# HRT1.net
KiCad netlist of a schematic drawn in Altium Designer
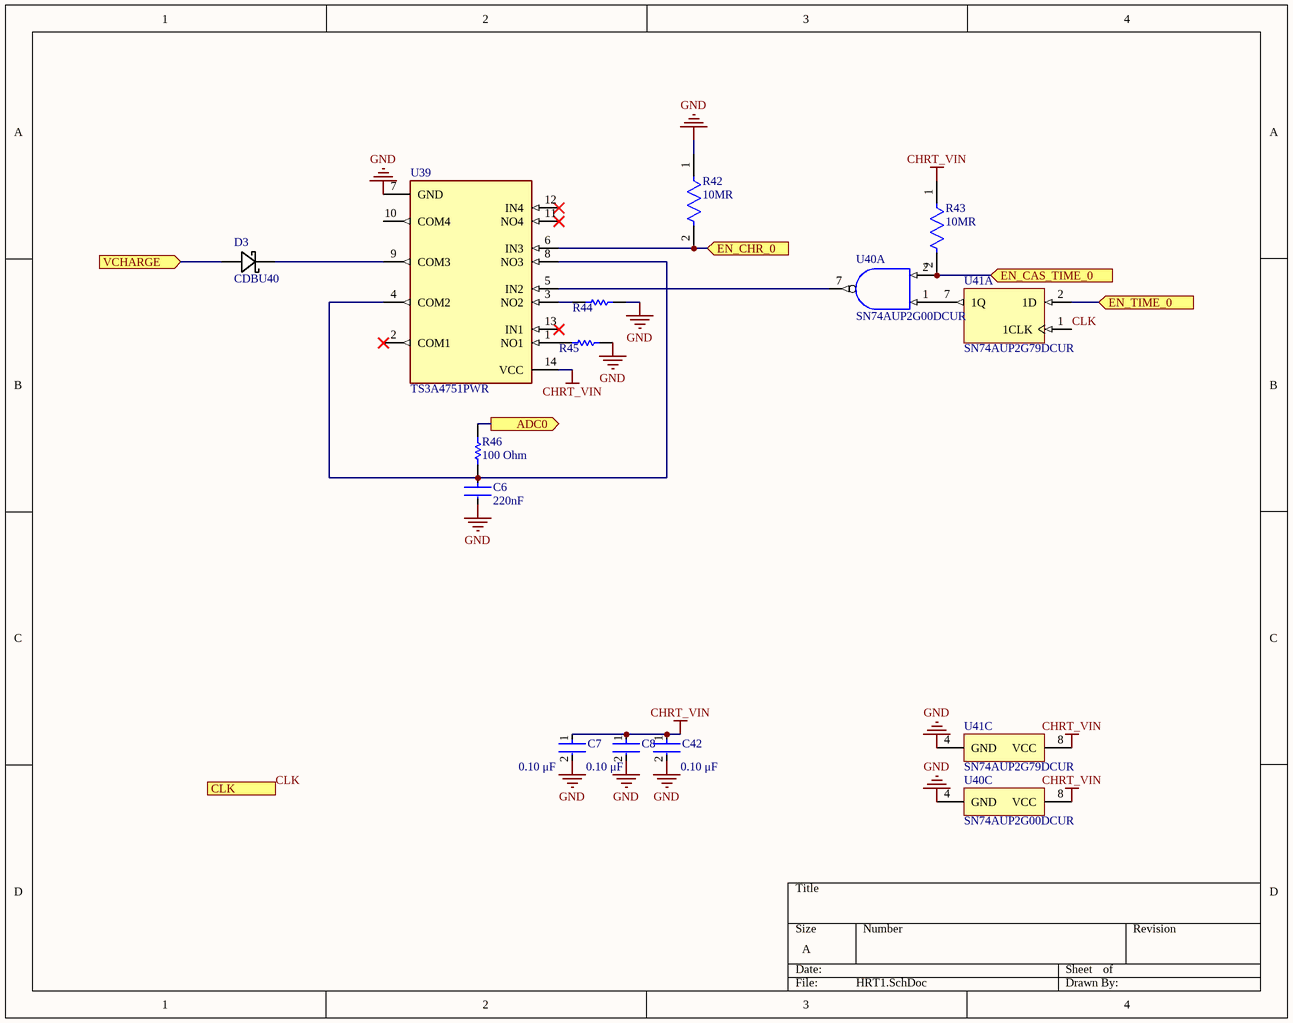
[diagram p0: HRT1.SchDoc]

(export (version "E")
  (design (tool "Eeschema 10.0.6"))
  (components
    (comp (ref "C6")
      (value "GRM155R71C224KA12D")
      (footprint "FP-GRM155-0_05-IPC_C")
      (description "Chip Multilayer Ceramic Capacitors for General Purpose, 0402, 0.22uF, X7R, 15%, 10%, 16V")
      (fields
        (field (name "CAPACITANCE") "220nF")
        (field (name "VOLTAGE") "16V")
        (field (name "TOLERANCE") "10%")
      )
      (libsource (lib "Altium Content Vault") (part "02cd4be3c70576c341d710602a673aa"))
    )
    (comp (ref "C7")
      (value "C0402C104K8PACTU")
      (footprint "FP-C0402-BB-MFG")
      (description "CAP CER 0.1UF 10V X5R 0402")
      (fields
        (field (name "CAPACITANCE") "0.10 μF")
        (field (name "MANUFACTURER") "Kemet")
        (field (name "TOLERANCE") "0.1")
      )
      (libsource (lib "Altium Content Vault") (part "b4654b650e69147ec39a6b967a45e02"))
    )
    (comp (ref "C8")
      (value "C0402C104K8PACTU")
      (footprint "FP-C0402-BB-MFG")
      (description "CAP CER 0.1UF 10V X5R 0402")
      (fields
        (field (name "CAPACITANCE") "0.10 μF")
        (field (name "MANUFACTURER") "Kemet")
        (field (name "TOLERANCE") "0.1")
      )
      (libsource (lib "Altium Content Vault") (part "b4654b650e69147ec39a6b967a45e02"))
    )
    (comp (ref "C42")
      (value "C0402C104K8PACTU")
      (footprint "FP-C0402-BB-MFG")
      (description "CAP CER 0.1UF 10V X5R 0402")
      (fields
        (field (name "CAPACITANCE") "0.10 μF")
        (field (name "MANUFACTURER") "Kemet")
        (field (name "TOLERANCE") "0.1")
      )
      (libsource (lib "Altium Content Vault") (part "b4654b650e69147ec39a6b967a45e02"))
    )
    (comp (ref "D3")
      (value "CDBU40")
      (footprint "CDBU")
      (description "No Description Available")
      (fields (field (name "COPYRIGHT") "Copyright (C) 2022 Ultra Librarian. All rights reserved."))
      (libsource (lib "CDBU40") (part "CDBU40"))
    )
    (comp (ref "R42")
      (value "CRCW040210M0JNED")
      (footprint "FP-CRCW0402-e3-IPC_C")
      (description "RES Thick Film, 10MΩ, 5%, 0.063W, 200ppm/°C, 0402")
      (fields (field (name "TOLERANCE") "5%") (field (name "RESISTANCE") "10MR"))
      (libsource (lib "Altium Content Vault") (part "1029c3af85768c4190bb7ad29bc67b5"))
    )
    (comp (ref "R43")
      (value "CRCW040210M0JNED")
      (footprint "FP-CRCW0402-e3-IPC_C")
      (description "RES Thick Film, 10MΩ, 5%, 0.063W, 200ppm/°C, 0402")
      (fields (field (name "TOLERANCE") "5%") (field (name "RESISTANCE") "10MR"))
      (libsource (lib "Altium Content Vault") (part "1029c3af85768c4190bb7ad29bc67b5"))
    )
    (comp (ref "R44")
      (value "CRCW040222R0FKED")
      (footprint "RESC1005X40X25LL05T05")
      (fields (field (name "MANUFACTURER") "Vishay Dale"))
      (libsource (lib "Altium Content Vault") (part "RES"))
    )
    (comp (ref "R45")
      (value "CRCW040222R0FKED")
      (footprint "RESC1005X40X25LL05T05")
      (fields (field (name "MANUFACTURER") "Vishay Dale"))
      (libsource (lib "Altium Content Vault") (part "RES"))
    )
    (comp (ref "R46")
      (value "ERJ-2RKF1000X")
      (footprint "RESC1005X40X25LL05T05")
      (description "Chip Resistor, 100 Ohm, +/- 1%, 100 mW, -55 to 155 degC, 0402 (1005 Metric), RoHS, Tape and Reel")
      (fields
        (field (name "MANUFACTURER") "Basic Passives")
        (field (name "TOLERANCE") "1%")
        (field (name "RESISTANCE") "100 Ohm")
      )
      (libsource (lib "Altium Content Vault") (part "RES-2"))
    )
    (comp (ref "U39")
      (value "TS3A4751PWR")
      (footprint "FP-PW0014A-IPC_C")
      (description "IC SWITCH QUAD SPST 14TSSOP")
      (libsource (lib "Altium Content Vault") (part "75fdcfb842d41a92b92a478e82e68ae"))
    )
    (comp (ref "U40")
      (value "SN74AUP2G00DCUR")
      (footprint "DCU0008A_L")
      (description "Low-Power Dual 2-Input Positive-NAND Gate, DCU0008A, LARGE T&R")
      (fields
        (field (name "GENERIC PART NUMBER") "SN74AUP2G00")
        (field (name "MANUFACTURER") "Texas Instruments")
      )
      (libsource (lib "Altium Content Vault") (part "TI-SN74XXX2GXXX-8"))
    )
    (comp (ref "U41")
      (value "SN74AUP2G79DCUR")
      (footprint "DCU0008A_L")
      (description "Low-Power Dual Positive-Edge-Triggered D-Type Flip-Flop, DCU0008A, LARGE T&R")
      (fields
        (field (name "MANUFACTURER") "Texas Instruments")
        (field (name "GENERIC PART NUMBER") "SN74AUP2G79")
      )
      (libsource (lib "Altium Content Vault") (part "TI-SN74XXX2G79-8_A"))
    )
  )
  (nets
    (net (code "1") (name "/ADC0") (class "Default")
      (node (ref "R46") (pin "2") (pinfunction "2_2") (pintype "passive"))
    )
    (net (code "2") (name "/CLK") (class "Default")
      (node (ref "U41") (pin "1") (pinfunction "1CLK_1") (pintype "input"))
    )
    (net (code "3") (name "/EN_CAS_TIME_0") (class "Default")
      (node (ref "R43") (pin "2") (pinfunction "2_2") (pintype "passive"))
      (node (ref "U40") (pin "2") (pinfunction "1B_2") (pintype "input"))
    )
    (net (code "4") (name "/EN_CHR_0") (class "Default")
      (node (ref "R42") (pin "2") (pinfunction "2_2") (pintype "passive"))
      (node (ref "U39") (pin "6") (pinfunction "IN3_6") (pintype "input"))
    )
    (net (code "5") (name "/EN_TIME_0") (class "Default")
      (node (ref "U41") (pin "2") (pinfunction "1D_2") (pintype "input"))
    )
    (net (code "6") (name "/VCHARGE") (class "Default")
      (node (ref "D3") (pin "2") (pinfunction "2_2") (pintype "passive"))
    )
    (net (code "7") (name "CHRT_VIN") (class "Default")
      (node (ref "C42") (pin "1") (pinfunction "1_1") (pintype "passive"))
      (node (ref "C7") (pin "1") (pinfunction "1_1") (pintype "passive"))
      (node (ref "C8") (pin "1") (pinfunction "1_1") (pintype "passive"))
      (node (ref "R43") (pin "1") (pinfunction "1_1") (pintype "passive"))
      (node (ref "U39") (pin "14") (pinfunction "VCC_14") (pintype "power_in"))
      (node (ref "U40") (pin "8") (pinfunction "VCC_8") (pintype "power_in"))
      (node (ref "U41") (pin "8") (pinfunction "VCC_8") (pintype "power_in"))
    )
    (net (code "8") (name "GND") (class "Default")
      (node (ref "C42") (pin "2") (pinfunction "2_2") (pintype "passive"))
      (node (ref "C6") (pin "2") (pinfunction "2_2") (pintype "passive"))
      (node (ref "C7") (pin "2") (pinfunction "2_2") (pintype "passive"))
      (node (ref "C8") (pin "2") (pinfunction "2_2") (pintype "passive"))
      (node (ref "R42") (pin "1") (pinfunction "1_1") (pintype "passive"))
      (node (ref "R44") (pin "2") (pinfunction "2_2") (pintype "passive"))
      (node (ref "R45") (pin "2") (pinfunction "2_2") (pintype "passive"))
      (node (ref "U39") (pin "7") (pinfunction "GND_7") (pintype "power_in"))
      (node (ref "U40") (pin "4") (pinfunction "GND_4") (pintype "power_in"))
      (node (ref "U41") (pin "4") (pinfunction "GND_4") (pintype "power_in"))
    )
    (net (code "9") (name "Net-(U39-COM2)") (class "Default")
      (node (ref "C6") (pin "1") (pinfunction "1_1") (pintype "passive"))
      (node (ref "R46") (pin "1") (pinfunction "1_1") (pintype "passive"))
      (node (ref "U39") (pin "4") (pinfunction "COM2_4") (pintype "output"))
      (node (ref "U39") (pin "8") (pinfunction "NO3_8") (pintype "input"))
    )
    (net (code "10") (name "Net-(U39-COM3)") (class "Default")
      (node (ref "D3") (pin "1") (pinfunction "1_1") (pintype "passive"))
      (node (ref "U39") (pin "9") (pinfunction "COM3_9") (pintype "output"))
    )
    (net (code "11") (name "Net-(U39-IN2)") (class "Default")
      (node (ref "U39") (pin "5") (pinfunction "IN2_5") (pintype "input"))
      (node (ref "U40") (pin "7") (pinfunction "1Y_7") (pintype "output"))
    )
    (net (code "12") (name "Net-(U39-NO1)") (class "Default")
      (node (ref "R45") (pin "1") (pinfunction "1_1") (pintype "passive"))
      (node (ref "U39") (pin "1") (pinfunction "NO1_1") (pintype "input"))
    )
    (net (code "13") (name "Net-(U39-NO2)") (class "Default")
      (node (ref "R44") (pin "1") (pinfunction "1_1") (pintype "passive"))
      (node (ref "U39") (pin "3") (pinfunction "NO2_3") (pintype "input"))
    )
    (net (code "14") (name "Net-(U40A-1A)") (class "Default")
      (node (ref "U40") (pin "1") (pinfunction "1A_1") (pintype "input"))
      (node (ref "U41") (pin "7") (pinfunction "1Q_7") (pintype "output"))
    )
    (net (code "15") (name "unconnected-(U39-COM1-Pad2)") (class "Default")
      (node (ref "U39") (pin "2") (pinfunction "COM1_2") (pintype "output+no_connect"))
    )
    (net (code "16") (name "unconnected-(U39-COM4-Pad10)") (class "Default")
      (node (ref "U39") (pin "10") (pinfunction "COM4_10") (pintype "output"))
    )
    (net (code "17") (name "unconnected-(U39-IN1-Pad13)") (class "Default")
      (node (ref "U39") (pin "13") (pinfunction "IN1_13") (pintype "input+no_connect"))
    )
    (net (code "18") (name "unconnected-(U39-IN4-Pad12)") (class "Default")
      (node (ref "U39") (pin "12") (pinfunction "IN4_12") (pintype "input+no_connect"))
    )
    (net (code "19") (name "unconnected-(U39-NO4-Pad11)") (class "Default")
      (node (ref "U39") (pin "11") (pinfunction "NO4_11") (pintype "input+no_connect"))
    )
  )
)
